# DMG-HDP-01_1-2.net
KiCad netlist of a schematic drawn in EAGLE
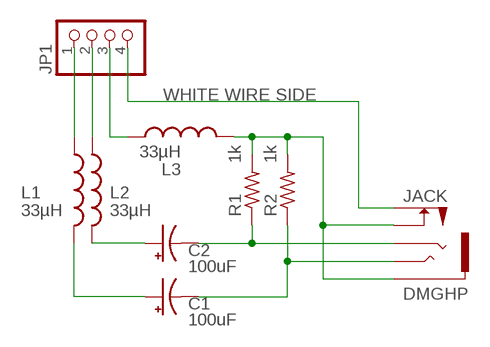
[diagram p0: schematic, sheet 1]

(export (version "E")
  (design (tool "Eeschema 10.0.6"))
  (components
    (comp (ref "C1")
      (value "100uF")
      (footprint "eagle-import:E2,5-5")
      (libsource (lib "eagle-import") (part "CPOL-USE2.5-5"))
    )
    (comp (ref "C2")
      (value "100uF")
      (footprint "eagle-import:E2,5-5")
      (libsource (lib "eagle-import") (part "CPOL-USE2.5-5"))
    )
    (comp (ref "JACK")
      (value "DMGHP")
      (footprint "eagle-import:DMG-HEADPHONE")
      (libsource (lib "eagle-import") (part "DMGHP"))
    )
    (comp (ref "JP1")
      (value "PINHD-1X4")
      (footprint "eagle-import:1X04")
      (libsource (lib "eagle-import") (part "PINHD-1X4"))
    )
    (comp (ref "L1")
      (value "33µH")
      (footprint "eagle-import:0204_7")
      (libsource (lib "eagle-import") (part "L-US0204/7"))
    )
    (comp (ref "L2")
      (value "33µH")
      (footprint "eagle-import:0204_7")
      (libsource (lib "eagle-import") (part "L-US0204/7"))
    )
    (comp (ref "L3")
      (value "33µH")
      (footprint "eagle-import:0204_7")
      (libsource (lib "eagle-import") (part "L-US0204/7"))
    )
    (comp (ref "R1")
      (value "1k")
      (footprint "eagle-import:R0603")
      (libsource (lib "eagle-import") (part "R-US_R0603"))
    )
    (comp (ref "R2")
      (value "1k")
      (footprint "eagle-import:R0603")
      (libsource (lib "eagle-import") (part "R-US_R0603"))
    )
  )
  (nets
    (net (code "1") (name "Net-(C1-Pad+)") (class "Default")
      (node (ref "C1") (pin "+") (pinfunction "+_+") (pintype "passive"))
      (node (ref "L1") (pin "2") (pinfunction "2_2") (pintype "passive"))
    )
    (net (code "2") (name "Net-(C1-Pad-)") (class "Default")
      (node (ref "C1") (pin "-") (pinfunction "-_-") (pintype "passive"))
      (node (ref "JACK") (pin "T") (pinfunction "T_T") (pintype "bidirectional"))
      (node (ref "R2") (pin "1") (pinfunction "1_1") (pintype "passive"))
    )
    (net (code "3") (name "Net-(C2-Pad+)") (class "Default")
      (node (ref "C2") (pin "+") (pinfunction "+_+") (pintype "passive"))
      (node (ref "L2") (pin "2") (pinfunction "2_2") (pintype "passive"))
    )
    (net (code "4") (name "Net-(C2-Pad-)") (class "Default")
      (node (ref "C2") (pin "-") (pinfunction "-_-") (pintype "passive"))
      (node (ref "JACK") (pin "R") (pinfunction "R_R") (pintype "bidirectional"))
      (node (ref "R1") (pin "1") (pinfunction "1_1") (pintype "passive"))
    )
    (net (code "5") (name "Net-(JACK-S)") (class "Default")
      (node (ref "JACK") (pin "GND") (pinfunction "S_GND") (pintype "bidirectional"))
      (node (ref "JACK") (pin "SWGND") (pinfunction "SWB_SWGND") (pintype "bidirectional"))
      (node (ref "L3") (pin "2") (pinfunction "2_2") (pintype "passive"))
      (node (ref "R1") (pin "2") (pinfunction "2_2") (pintype "passive"))
      (node (ref "R2") (pin "2") (pinfunction "2_2") (pintype "passive"))
    )
    (net (code "6") (name "Net-(JACK-SWA)") (class "Default")
      (node (ref "JACK") (pin "SW") (pinfunction "SWA_SW") (pintype "bidirectional"))
      (node (ref "JP1") (pin "4") (pinfunction "4_4") (pintype "passive"))
    )
    (net (code "7") (name "Net-(JP1-Pad1)") (class "Default")
      (node (ref "JP1") (pin "1") (pinfunction "1_1") (pintype "passive"))
      (node (ref "L1") (pin "1") (pinfunction "1_1") (pintype "passive"))
    )
    (net (code "8") (name "Net-(JP1-Pad2)") (class "Default")
      (node (ref "JP1") (pin "2") (pinfunction "2_2") (pintype "passive"))
      (node (ref "L2") (pin "1") (pinfunction "1_1") (pintype "passive"))
    )
    (net (code "9") (name "Net-(JP1-Pad3)") (class "Default")
      (node (ref "JP1") (pin "3") (pinfunction "3_3") (pintype "passive"))
      (node (ref "L3") (pin "1") (pinfunction "1_1") (pintype "passive"))
    )
  )
)
